# DoubleWing.net
KiCad netlist of a schematic drawn in EAGLE
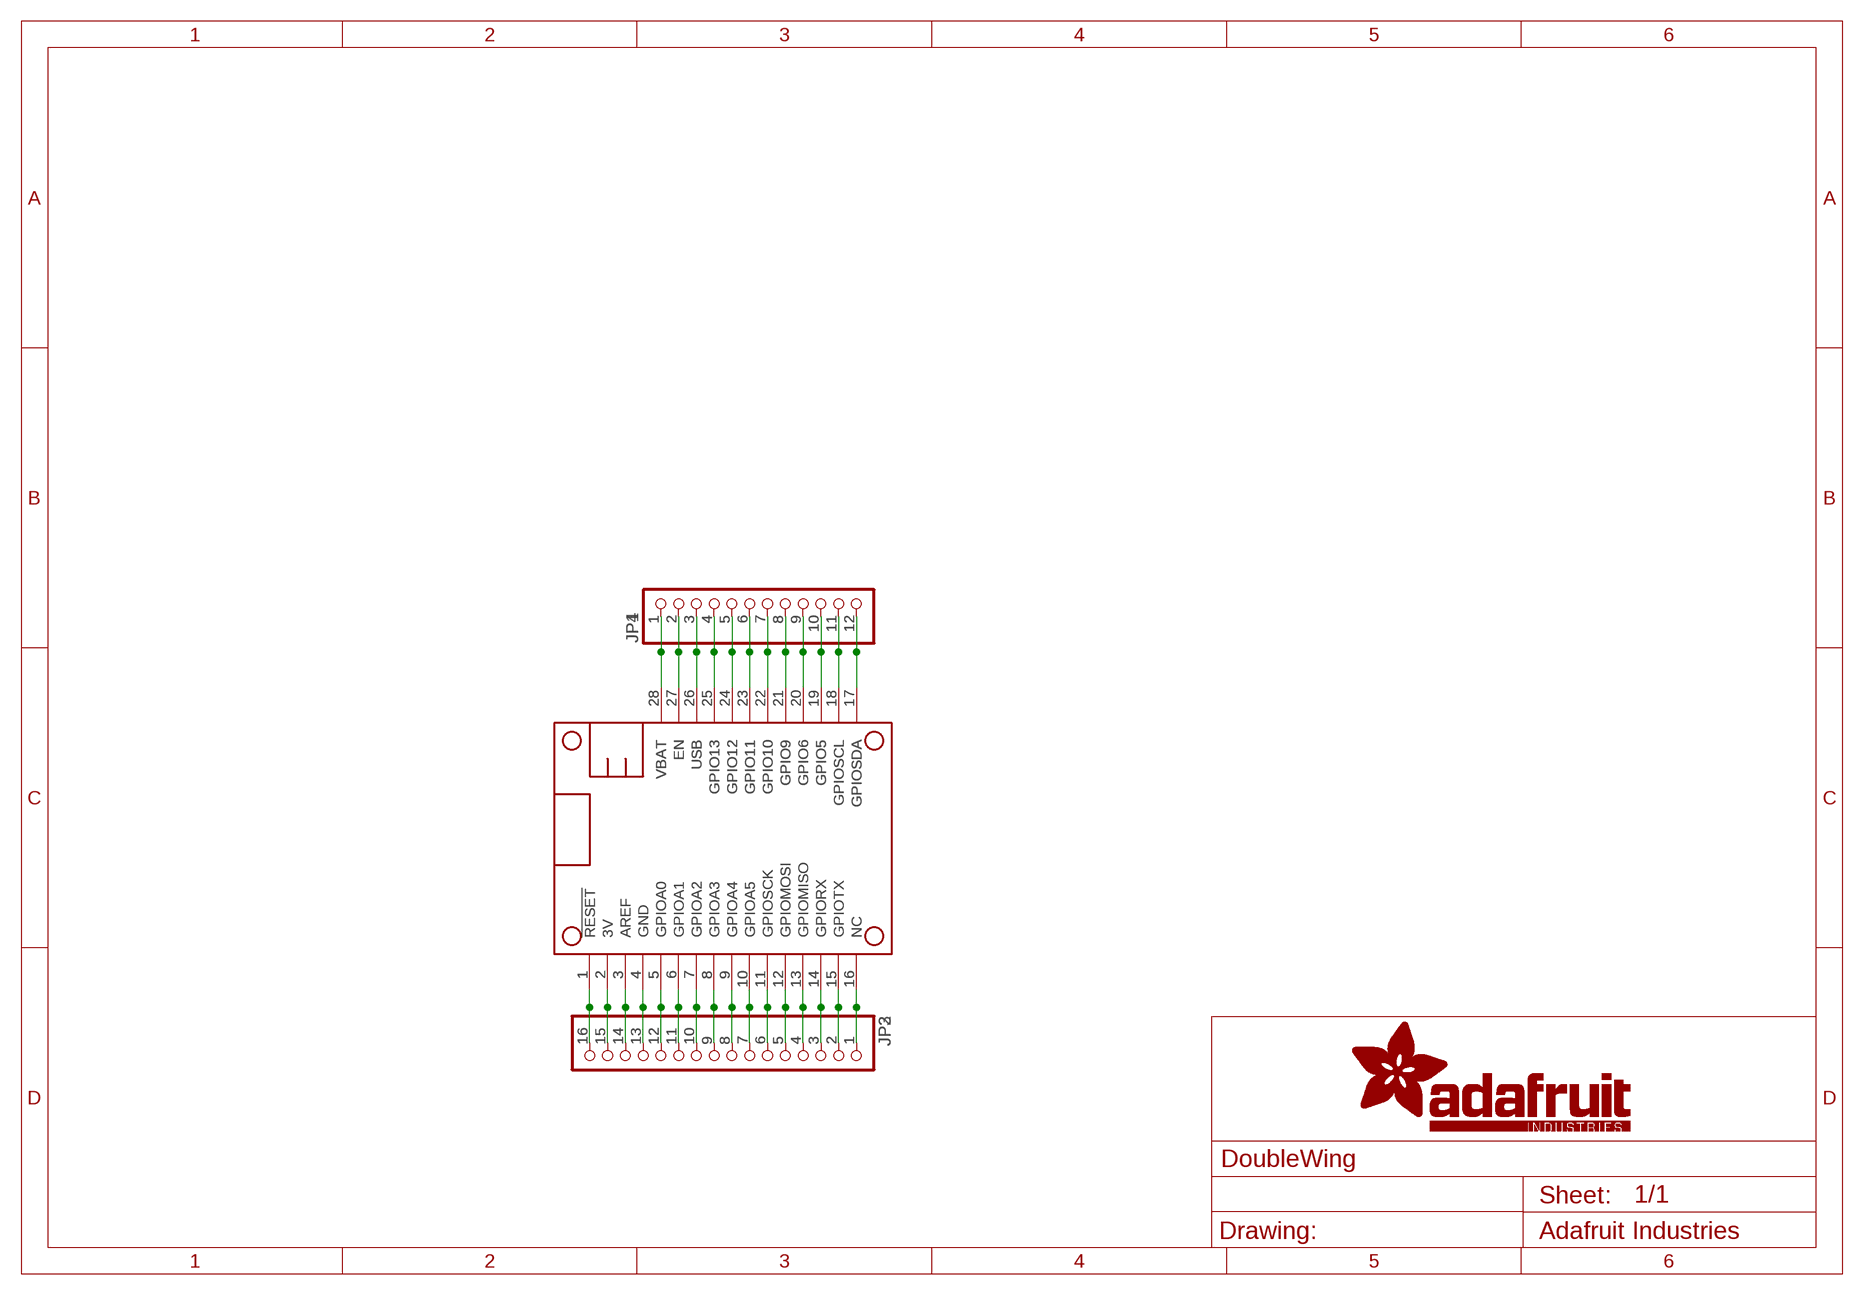
[diagram p0: schematic, sheet 1]

(export (version "E")
  (design (tool "Eeschema 10.0.6"))
  (components
    (comp (ref "JP1")
      (value "HEADER-1X1276MIL")
      (footprint "eagle-import:1X12_ROUND_76MIL")
      (libsource (lib "eagle-import") (part "HEADER-1X1276MIL"))
    )
    (comp (ref "JP2")
      (value "HEADER-1X16_76MIL")
      (footprint "eagle-import:1X16_ROUND_76MIL")
      (libsource (lib "eagle-import") (part "HEADER-1X16_76MIL"))
    )
    (comp (ref "JP3")
      (value "HEADER-1X16_76MIL")
      (footprint "eagle-import:1X16_ROUND_76MIL")
      (libsource (lib "eagle-import") (part "HEADER-1X16_76MIL"))
    )
    (comp (ref "JP4")
      (value "HEADER-1X1276MIL")
      (footprint "eagle-import:1X12_ROUND_76MIL")
      (libsource (lib "eagle-import") (part "HEADER-1X1276MIL"))
    )
    (comp (ref "MS1")
      (value "FEATHERWING_NODIM")
      (footprint "eagle-import:FEATHERWING_DIM")
      (libsource (lib "eagle-import") (part "FEATHERWING_NODIM"))
    )
    (comp (ref "MS2")
      (value "FEATHERWING_NODIM")
      (footprint "eagle-import:FEATHERWING_DIM")
      (libsource (lib "eagle-import") (part "FEATHERWING_NODIM"))
    )
  )
  (nets
    (net (code "1") (name "Net-(MS1-3V)") (class "Default")
      (node (ref "JP2") (pin "15") (pinfunction "15_15") (pintype "passive"))
      (node (ref "JP3") (pin "15") (pinfunction "15_15") (pintype "passive"))
      (node (ref "MS1") (pin "2") (pinfunction "3V_2") (pintype "power_in"))
      (node (ref "MS2") (pin "2") (pinfunction "3V_2") (pintype "power_in"))
    )
    (net (code "2") (name "Net-(MS1-AREF)") (class "Default")
      (node (ref "JP2") (pin "14") (pinfunction "14_14") (pintype "passive"))
      (node (ref "JP3") (pin "14") (pinfunction "14_14") (pintype "passive"))
      (node (ref "MS1") (pin "3") (pinfunction "AREF_3") (pintype "passive"))
      (node (ref "MS2") (pin "3") (pinfunction "AREF_3") (pintype "passive"))
    )
    (net (code "3") (name "Net-(MS1-EN)") (class "Default")
      (node (ref "JP1") (pin "2") (pinfunction "2_2") (pintype "passive"))
      (node (ref "JP4") (pin "2") (pinfunction "2_2") (pintype "passive"))
      (node (ref "MS1") (pin "27") (pinfunction "EN_27") (pintype "passive"))
      (node (ref "MS2") (pin "27") (pinfunction "EN_27") (pintype "passive"))
    )
    (net (code "4") (name "Net-(MS1-GND)") (class "Default")
      (node (ref "JP2") (pin "13") (pinfunction "13_13") (pintype "passive"))
      (node (ref "JP3") (pin "13") (pinfunction "13_13") (pintype "passive"))
      (node (ref "MS1") (pin "4") (pinfunction "GND_4") (pintype "power_in"))
      (node (ref "MS2") (pin "4") (pinfunction "GND_4") (pintype "power_in"))
    )
    (net (code "5") (name "Net-(MS1-GPIO5)") (class "Default")
      (node (ref "JP1") (pin "10") (pinfunction "10_10") (pintype "passive"))
      (node (ref "JP4") (pin "10") (pinfunction "10_10") (pintype "passive"))
      (node (ref "MS1") (pin "19") (pinfunction "GPIO5_19") (pintype "bidirectional"))
      (node (ref "MS2") (pin "19") (pinfunction "GPIO5_19") (pintype "bidirectional"))
    )
    (net (code "6") (name "Net-(MS1-GPIO6)") (class "Default")
      (node (ref "JP1") (pin "9") (pinfunction "9_9") (pintype "passive"))
      (node (ref "JP4") (pin "9") (pinfunction "9_9") (pintype "passive"))
      (node (ref "MS1") (pin "20") (pinfunction "GPIO6_20") (pintype "bidirectional"))
      (node (ref "MS2") (pin "20") (pinfunction "GPIO6_20") (pintype "bidirectional"))
    )
    (net (code "7") (name "Net-(MS1-GPIO9)") (class "Default")
      (node (ref "JP1") (pin "8") (pinfunction "8_8") (pintype "passive"))
      (node (ref "JP4") (pin "8") (pinfunction "8_8") (pintype "passive"))
      (node (ref "MS1") (pin "21") (pinfunction "GPIO9_21") (pintype "bidirectional"))
      (node (ref "MS2") (pin "21") (pinfunction "GPIO9_21") (pintype "bidirectional"))
    )
    (net (code "8") (name "Net-(MS1-GPIO10)") (class "Default")
      (node (ref "JP1") (pin "7") (pinfunction "7_7") (pintype "passive"))
      (node (ref "JP4") (pin "7") (pinfunction "7_7") (pintype "passive"))
      (node (ref "MS1") (pin "22") (pinfunction "GPIO10_22") (pintype "bidirectional"))
      (node (ref "MS2") (pin "22") (pinfunction "GPIO10_22") (pintype "bidirectional"))
    )
    (net (code "9") (name "Net-(MS1-GPIO11)") (class "Default")
      (node (ref "JP1") (pin "6") (pinfunction "6_6") (pintype "passive"))
      (node (ref "JP4") (pin "6") (pinfunction "6_6") (pintype "passive"))
      (node (ref "MS1") (pin "23") (pinfunction "GPIO11_23") (pintype "bidirectional"))
      (node (ref "MS2") (pin "23") (pinfunction "GPIO11_23") (pintype "bidirectional"))
    )
    (net (code "10") (name "Net-(MS1-GPIO12)") (class "Default")
      (node (ref "JP1") (pin "5") (pinfunction "5_5") (pintype "passive"))
      (node (ref "JP4") (pin "5") (pinfunction "5_5") (pintype "passive"))
      (node (ref "MS1") (pin "24") (pinfunction "GPIO12_24") (pintype "bidirectional"))
      (node (ref "MS2") (pin "24") (pinfunction "GPIO12_24") (pintype "bidirectional"))
    )
    (net (code "11") (name "Net-(MS1-GPIO13)") (class "Default")
      (node (ref "JP1") (pin "4") (pinfunction "4_4") (pintype "passive"))
      (node (ref "JP4") (pin "4") (pinfunction "4_4") (pintype "passive"))
      (node (ref "MS1") (pin "25") (pinfunction "GPIO13_25") (pintype "bidirectional"))
      (node (ref "MS2") (pin "25") (pinfunction "GPIO13_25") (pintype "bidirectional"))
    )
    (net (code "12") (name "Net-(MS1-GPIOA0)") (class "Default")
      (node (ref "JP2") (pin "12") (pinfunction "12_12") (pintype "passive"))
      (node (ref "JP3") (pin "12") (pinfunction "12_12") (pintype "passive"))
      (node (ref "MS1") (pin "5") (pinfunction "GPIOA0_5") (pintype "bidirectional"))
      (node (ref "MS2") (pin "5") (pinfunction "GPIOA0_5") (pintype "bidirectional"))
    )
    (net (code "13") (name "Net-(MS1-GPIOA1)") (class "Default")
      (node (ref "JP2") (pin "11") (pinfunction "11_11") (pintype "passive"))
      (node (ref "JP3") (pin "11") (pinfunction "11_11") (pintype "passive"))
      (node (ref "MS1") (pin "6") (pinfunction "GPIOA1_6") (pintype "bidirectional"))
      (node (ref "MS2") (pin "6") (pinfunction "GPIOA1_6") (pintype "bidirectional"))
    )
    (net (code "14") (name "Net-(MS1-GPIOA2)") (class "Default")
      (node (ref "JP2") (pin "10") (pinfunction "10_10") (pintype "passive"))
      (node (ref "JP3") (pin "10") (pinfunction "10_10") (pintype "passive"))
      (node (ref "MS1") (pin "7") (pinfunction "GPIOA2_7") (pintype "bidirectional"))
      (node (ref "MS2") (pin "7") (pinfunction "GPIOA2_7") (pintype "bidirectional"))
    )
    (net (code "15") (name "Net-(MS1-GPIOA3)") (class "Default")
      (node (ref "JP2") (pin "9") (pinfunction "9_9") (pintype "passive"))
      (node (ref "JP3") (pin "9") (pinfunction "9_9") (pintype "passive"))
      (node (ref "MS1") (pin "8") (pinfunction "GPIOA3_8") (pintype "bidirectional"))
      (node (ref "MS2") (pin "8") (pinfunction "GPIOA3_8") (pintype "bidirectional"))
    )
    (net (code "16") (name "Net-(MS1-GPIOA4)") (class "Default")
      (node (ref "JP2") (pin "8") (pinfunction "8_8") (pintype "passive"))
      (node (ref "JP3") (pin "8") (pinfunction "8_8") (pintype "passive"))
      (node (ref "MS1") (pin "9") (pinfunction "GPIOA4_9") (pintype "bidirectional"))
      (node (ref "MS2") (pin "9") (pinfunction "GPIOA4_9") (pintype "bidirectional"))
    )
    (net (code "17") (name "Net-(MS1-GPIOA5)") (class "Default")
      (node (ref "JP2") (pin "7") (pinfunction "7_7") (pintype "passive"))
      (node (ref "JP3") (pin "7") (pinfunction "7_7") (pintype "passive"))
      (node (ref "MS1") (pin "10") (pinfunction "GPIOA5_10") (pintype "bidirectional"))
      (node (ref "MS2") (pin "10") (pinfunction "GPIOA5_10") (pintype "bidirectional"))
    )
    (net (code "18") (name "Net-(MS1-GPIOMISO)") (class "Default")
      (node (ref "JP2") (pin "4") (pinfunction "4_4") (pintype "passive"))
      (node (ref "JP3") (pin "4") (pinfunction "4_4") (pintype "passive"))
      (node (ref "MS1") (pin "13") (pinfunction "GPIOMISO_13") (pintype "bidirectional"))
      (node (ref "MS2") (pin "13") (pinfunction "GPIOMISO_13") (pintype "bidirectional"))
    )
    (net (code "19") (name "Net-(MS1-GPIOMOSI)") (class "Default")
      (node (ref "JP2") (pin "5") (pinfunction "5_5") (pintype "passive"))
      (node (ref "JP3") (pin "5") (pinfunction "5_5") (pintype "passive"))
      (node (ref "MS1") (pin "12") (pinfunction "GPIOMOSI_12") (pintype "bidirectional"))
      (node (ref "MS2") (pin "12") (pinfunction "GPIOMOSI_12") (pintype "bidirectional"))
    )
    (net (code "20") (name "Net-(MS1-GPIORX)") (class "Default")
      (node (ref "JP2") (pin "3") (pinfunction "3_3") (pintype "passive"))
      (node (ref "JP3") (pin "3") (pinfunction "3_3") (pintype "passive"))
      (node (ref "MS1") (pin "14") (pinfunction "GPIORX_14") (pintype "bidirectional"))
      (node (ref "MS2") (pin "14") (pinfunction "GPIORX_14") (pintype "bidirectional"))
    )
    (net (code "21") (name "Net-(MS1-GPIOSCK)") (class "Default")
      (node (ref "JP2") (pin "6") (pinfunction "6_6") (pintype "passive"))
      (node (ref "JP3") (pin "6") (pinfunction "6_6") (pintype "passive"))
      (node (ref "MS1") (pin "11") (pinfunction "GPIOSCK_11") (pintype "bidirectional"))
      (node (ref "MS2") (pin "11") (pinfunction "GPIOSCK_11") (pintype "bidirectional"))
    )
    (net (code "22") (name "Net-(MS1-GPIOSCL)") (class "Default")
      (node (ref "JP1") (pin "11") (pinfunction "11_11") (pintype "passive"))
      (node (ref "JP4") (pin "11") (pinfunction "11_11") (pintype "passive"))
      (node (ref "MS1") (pin "18") (pinfunction "GPIOSCL_18") (pintype "bidirectional"))
      (node (ref "MS2") (pin "18") (pinfunction "GPIOSCL_18") (pintype "bidirectional"))
    )
    (net (code "23") (name "Net-(MS1-GPIOSDA)") (class "Default")
      (node (ref "JP1") (pin "12") (pinfunction "12_12") (pintype "passive"))
      (node (ref "JP4") (pin "12") (pinfunction "12_12") (pintype "passive"))
      (node (ref "MS1") (pin "17") (pinfunction "GPIOSDA_17") (pintype "bidirectional"))
      (node (ref "MS2") (pin "17") (pinfunction "GPIOSDA_17") (pintype "bidirectional"))
    )
    (net (code "24") (name "Net-(MS1-GPIOTX)") (class "Default")
      (node (ref "JP2") (pin "2") (pinfunction "2_2") (pintype "passive"))
      (node (ref "JP3") (pin "2") (pinfunction "2_2") (pintype "passive"))
      (node (ref "MS1") (pin "15") (pinfunction "GPIOTX_15") (pintype "bidirectional"))
      (node (ref "MS2") (pin "15") (pinfunction "GPIOTX_15") (pintype "bidirectional"))
    )
    (net (code "25") (name "Net-(MS1-NC)") (class "Default")
      (node (ref "JP2") (pin "1") (pinfunction "1_1") (pintype "passive"))
      (node (ref "JP3") (pin "1") (pinfunction "1_1") (pintype "passive"))
      (node (ref "MS1") (pin "16") (pinfunction "NC_16") (pintype "passive"))
      (node (ref "MS2") (pin "16") (pinfunction "NC_16") (pintype "passive"))
    )
    (net (code "26") (name "Net-(MS1-USB)") (class "Default")
      (node (ref "JP1") (pin "3") (pinfunction "3_3") (pintype "passive"))
      (node (ref "JP4") (pin "3") (pinfunction "3_3") (pintype "passive"))
      (node (ref "MS1") (pin "26") (pinfunction "USB_26") (pintype "power_in"))
      (node (ref "MS2") (pin "26") (pinfunction "USB_26") (pintype "power_in"))
    )
    (net (code "27") (name "Net-(MS1-VBAT)") (class "Default")
      (node (ref "JP1") (pin "1") (pinfunction "1_1") (pintype "passive"))
      (node (ref "JP4") (pin "1") (pinfunction "1_1") (pintype "passive"))
      (node (ref "MS1") (pin "28") (pinfunction "VBAT_28") (pintype "power_in"))
      (node (ref "MS2") (pin "28") (pinfunction "VBAT_28") (pintype "power_in"))
    )
    (net (code "28") (name "Net-(MS1-~{RESET})") (class "Default")
      (node (ref "JP2") (pin "16") (pinfunction "16_16") (pintype "passive"))
      (node (ref "JP3") (pin "16") (pinfunction "16_16") (pintype "passive"))
      (node (ref "MS1") (pin "1") (pinfunction "~{RESET}_1") (pintype "input"))
      (node (ref "MS2") (pin "1") (pinfunction "~{RESET}_1") (pintype "input"))
    )
  )
)
